# Cross-LogIO.net
KiCad netlist of a schematic drawn in Altium Designer
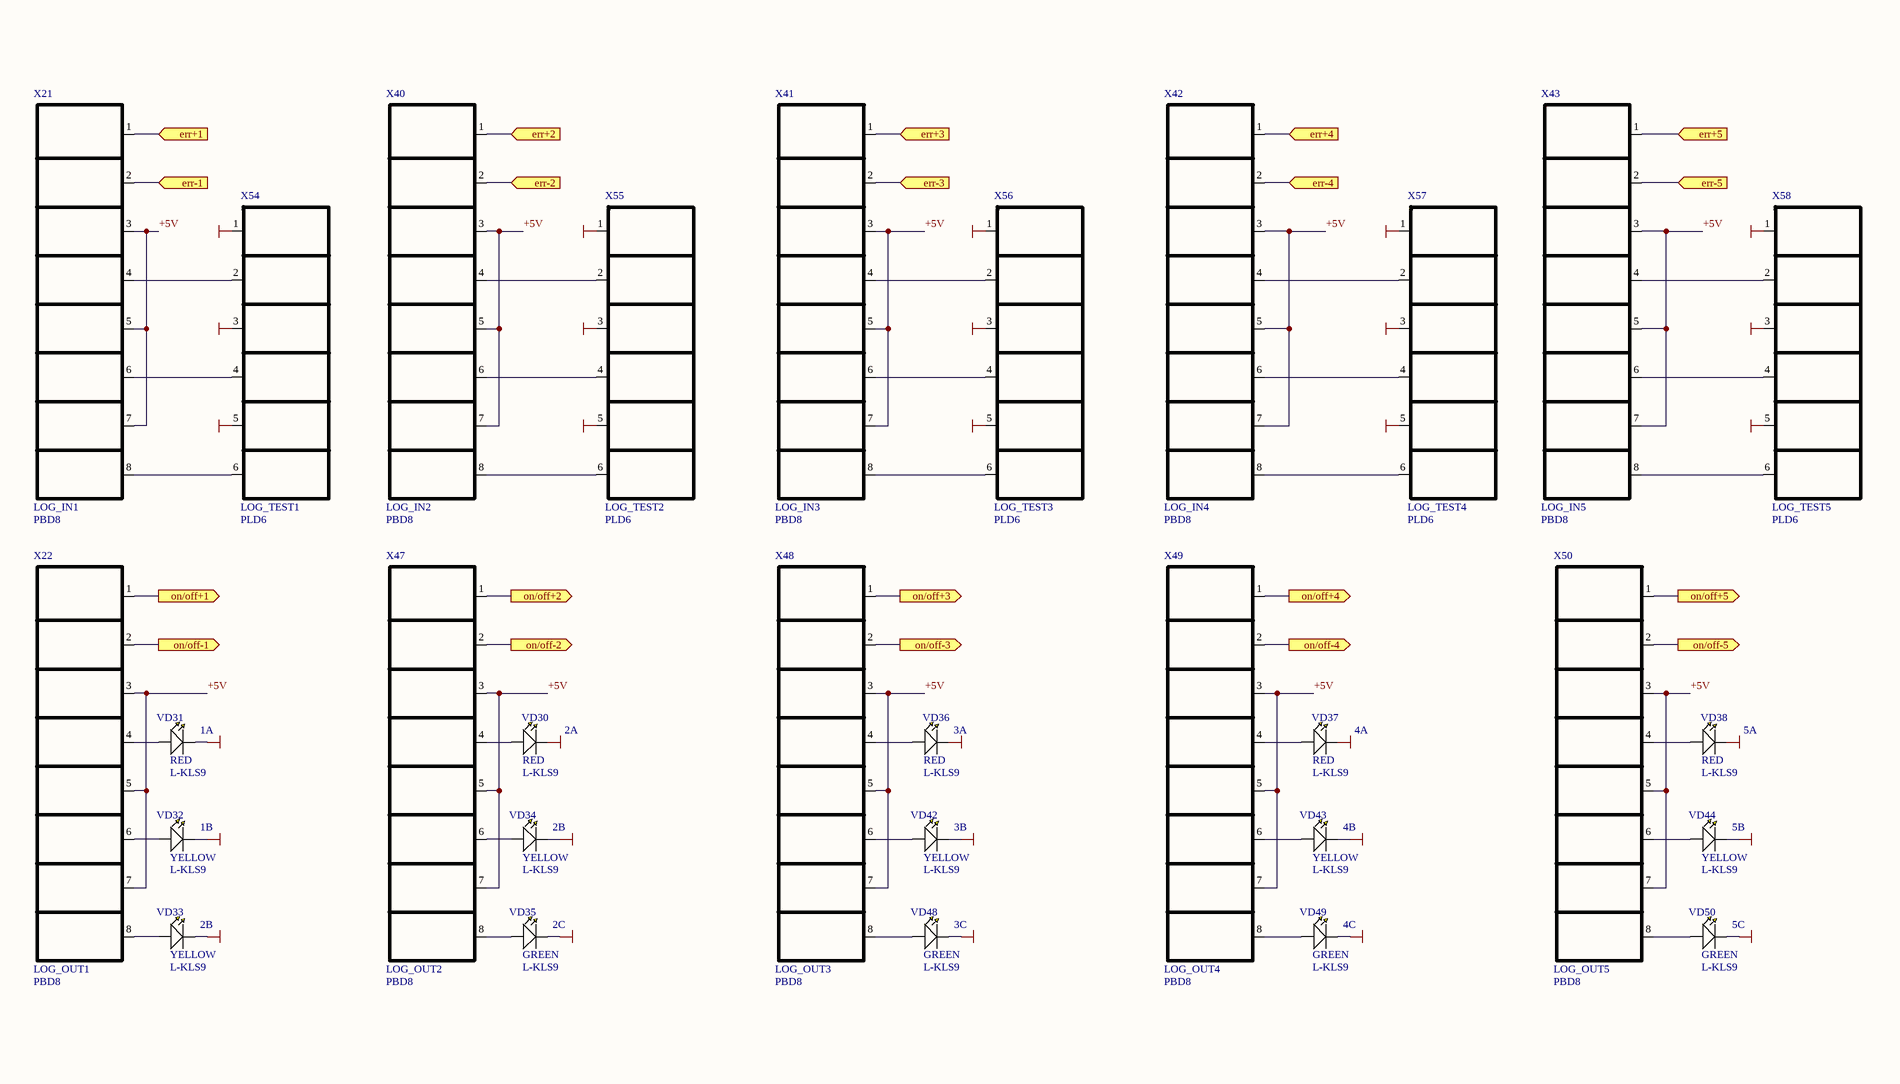
[diagram p0: Cross-LogIO.SchDoc, left]
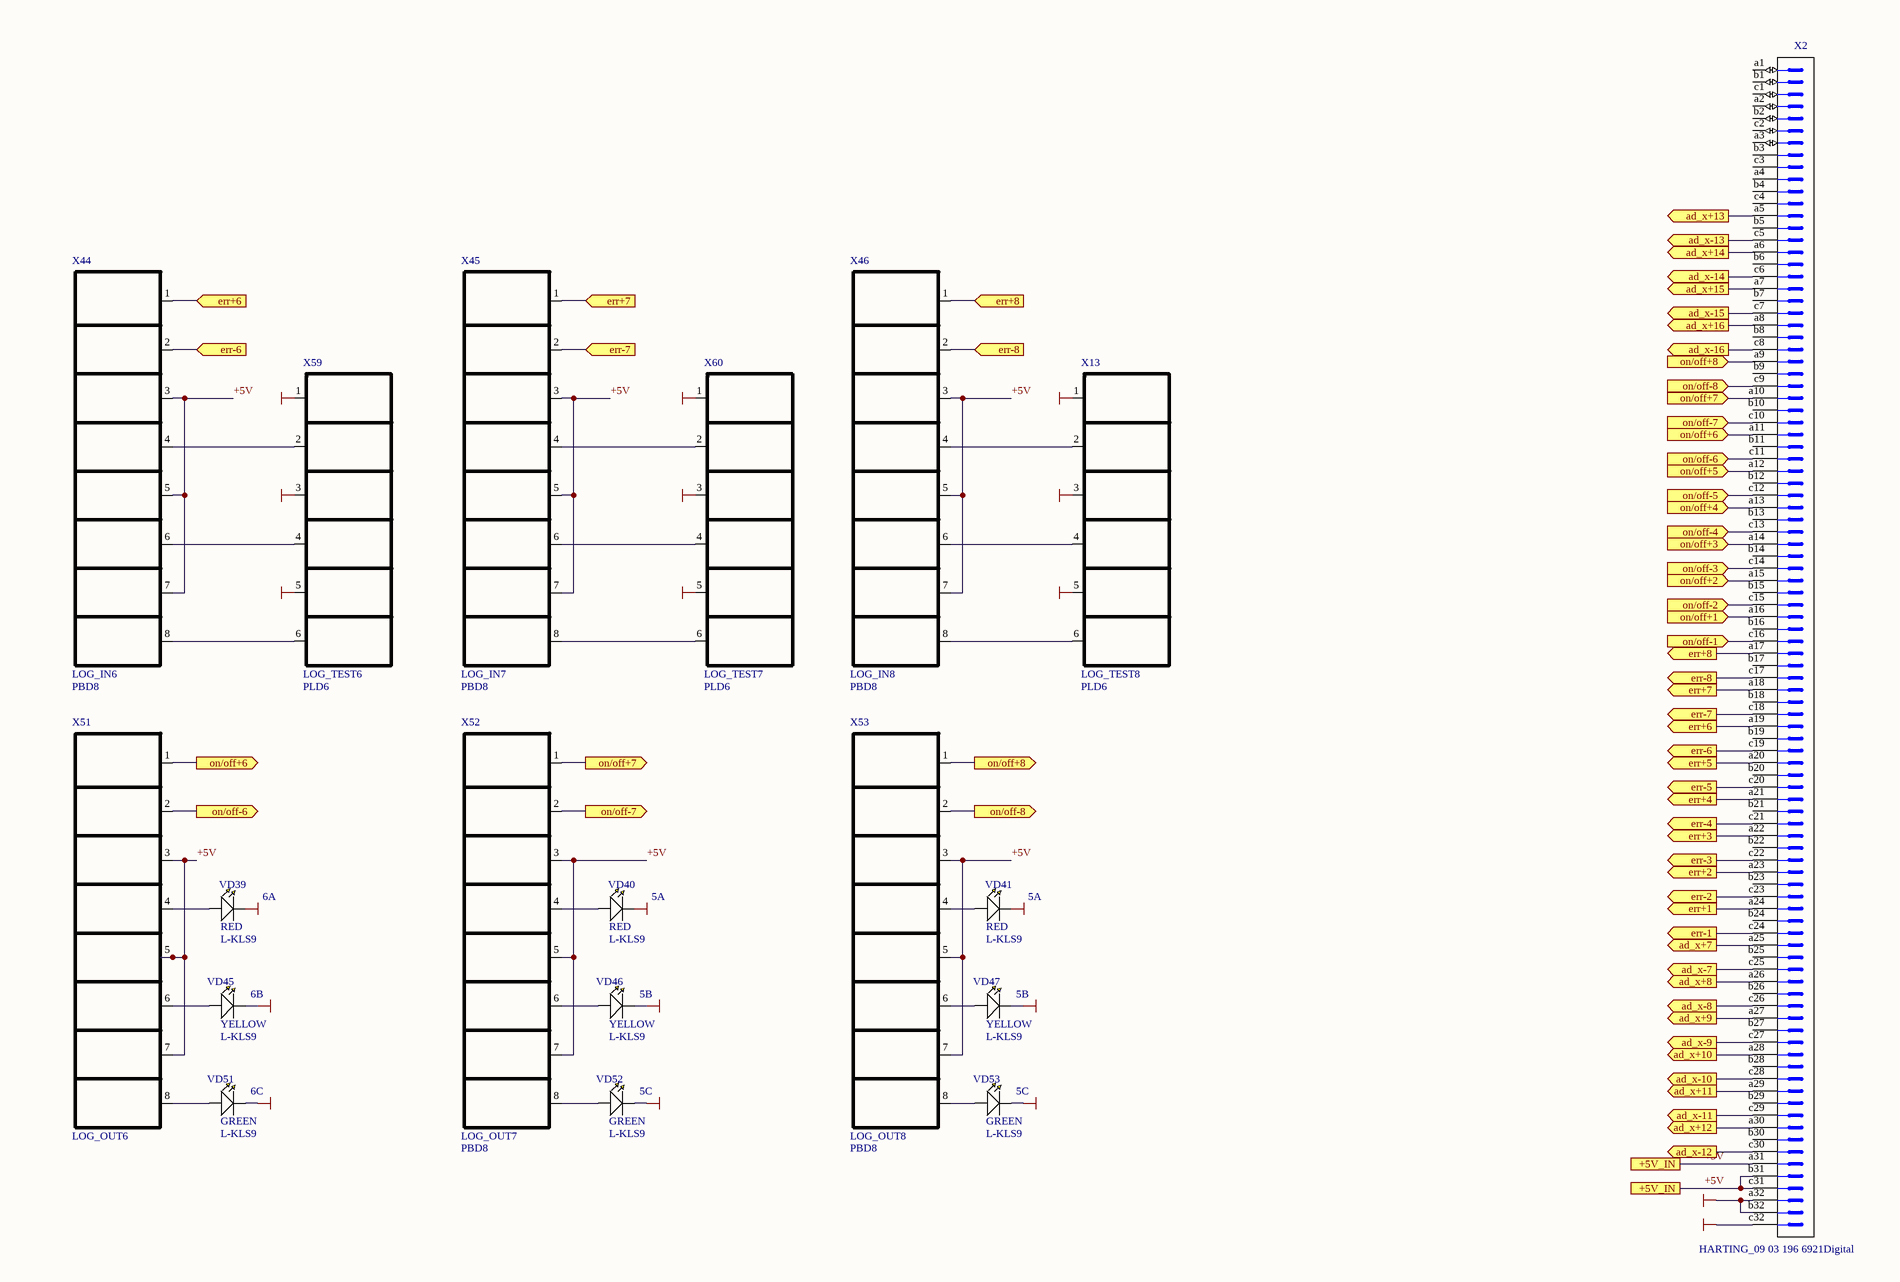
[diagram p1: Cross-LogIO.SchDoc, right]

(export (version "E")
  (design (tool "Eeschema 10.0.6"))
  (components
    (comp (ref "VD30")
      (value "2A")
      (footprint "LED0603")
      (description "Chip LED SMD 0603")
      (fields (field (name "COLOR") "RED") (field (name "DEVICE") "L-KLS9"))
      (libsource (lib "L1") (part "L-KLS9-T0603"))
    )
    (comp (ref "VD31")
      (value "1A")
      (footprint "LED0603")
      (description "Chip LED SMD 0603")
      (fields (field (name "COLOR") "RED") (field (name "DEVICE") "L-KLS9"))
      (libsource (lib "L1") (part "L-KLS9-T0603"))
    )
    (comp (ref "VD32")
      (value "1B")
      (footprint "LED0603")
      (description "Chip LED SMD 0603")
      (fields (field (name "COLOR") "YELLOW") (field (name "DEVICE") "L-KLS9"))
      (libsource (lib "L1") (part "L-KLS9-T0603"))
    )
    (comp (ref "VD33")
      (value "2B")
      (footprint "LED0603")
      (description "Chip LED SMD 0603")
      (fields (field (name "COLOR") "YELLOW") (field (name "DEVICE") "L-KLS9"))
      (libsource (lib "L1") (part "L-KLS9-T0603"))
    )
    (comp (ref "VD34")
      (value "2B")
      (footprint "LED0603")
      (description "Chip LED SMD 0603")
      (fields (field (name "COLOR") "YELLOW") (field (name "DEVICE") "L-KLS9"))
      (libsource (lib "L1") (part "L-KLS9-T0603"))
    )
    (comp (ref "VD35")
      (value "2C")
      (footprint "LED0603")
      (description "Chip LED SMD 0603")
      (fields (field (name "COLOR") "GREEN") (field (name "DEVICE") "L-KLS9"))
      (libsource (lib "L1") (part "L-KLS9-T0603"))
    )
    (comp (ref "VD36")
      (value "3A")
      (footprint "LED0603")
      (description "Chip LED SMD 0603")
      (fields (field (name "COLOR") "RED") (field (name "DEVICE") "L-KLS9"))
      (libsource (lib "L1") (part "L-KLS9-T0603"))
    )
    (comp (ref "VD37")
      (value "4A")
      (footprint "LED0603")
      (description "Chip LED SMD 0603")
      (fields (field (name "COLOR") "RED") (field (name "DEVICE") "L-KLS9"))
      (libsource (lib "L1") (part "L-KLS9-T0603"))
    )
    (comp (ref "VD38")
      (value "5A")
      (footprint "LED0603")
      (description "Chip LED SMD 0603")
      (fields (field (name "COLOR") "RED") (field (name "DEVICE") "L-KLS9"))
      (libsource (lib "L1") (part "L-KLS9-T0603"))
    )
    (comp (ref "VD39")
      (value "6A")
      (footprint "LED0603")
      (description "Chip LED SMD 0603")
      (fields (field (name "COLOR") "RED") (field (name "DEVICE") "L-KLS9"))
      (libsource (lib "L1") (part "L-KLS9-T0603"))
    )
    (comp (ref "VD40")
      (value "5A")
      (footprint "LED0603")
      (description "Chip LED SMD 0603")
      (fields (field (name "COLOR") "RED") (field (name "DEVICE") "L-KLS9"))
      (libsource (lib "L1") (part "L-KLS9-T0603"))
    )
    (comp (ref "VD41")
      (value "5A")
      (footprint "LED0603")
      (description "Chip LED SMD 0603")
      (fields (field (name "COLOR") "RED") (field (name "DEVICE") "L-KLS9"))
      (libsource (lib "L1") (part "L-KLS9-T0603"))
    )
    (comp (ref "VD42")
      (value "3B")
      (footprint "LED0603")
      (description "Chip LED SMD 0603")
      (fields (field (name "COLOR") "YELLOW") (field (name "DEVICE") "L-KLS9"))
      (libsource (lib "L1") (part "L-KLS9-T0603"))
    )
    (comp (ref "VD43")
      (value "4B")
      (footprint "LED0603")
      (description "Chip LED SMD 0603")
      (fields (field (name "COLOR") "YELLOW") (field (name "DEVICE") "L-KLS9"))
      (libsource (lib "L1") (part "L-KLS9-T0603"))
    )
    (comp (ref "VD44")
      (value "5B")
      (footprint "LED0603")
      (description "Chip LED SMD 0603")
      (fields (field (name "COLOR") "YELLOW") (field (name "DEVICE") "L-KLS9"))
      (libsource (lib "L1") (part "L-KLS9-T0603"))
    )
    (comp (ref "VD45")
      (value "6B")
      (footprint "LED0603")
      (description "Chip LED SMD 0603")
      (fields (field (name "COLOR") "YELLOW") (field (name "DEVICE") "L-KLS9"))
      (libsource (lib "L1") (part "L-KLS9-T0603"))
    )
    (comp (ref "VD46")
      (value "5B")
      (footprint "LED0603")
      (description "Chip LED SMD 0603")
      (fields (field (name "COLOR") "YELLOW") (field (name "DEVICE") "L-KLS9"))
      (libsource (lib "L1") (part "L-KLS9-T0603"))
    )
    (comp (ref "VD47")
      (value "5B")
      (footprint "LED0603")
      (description "Chip LED SMD 0603")
      (fields (field (name "COLOR") "YELLOW") (field (name "DEVICE") "L-KLS9"))
      (libsource (lib "L1") (part "L-KLS9-T0603"))
    )
    (comp (ref "VD48")
      (value "3C")
      (footprint "LED0603")
      (description "Chip LED SMD 0603")
      (fields (field (name "COLOR") "GREEN") (field (name "DEVICE") "L-KLS9"))
      (libsource (lib "L1") (part "L-KLS9-T0603"))
    )
    (comp (ref "VD49")
      (value "4C")
      (footprint "LED0603")
      (description "Chip LED SMD 0603")
      (fields (field (name "COLOR") "GREEN") (field (name "DEVICE") "L-KLS9"))
      (libsource (lib "L1") (part "L-KLS9-T0603"))
    )
    (comp (ref "VD50")
      (value "5C")
      (footprint "LED0603")
      (description "Chip LED SMD 0603")
      (fields (field (name "COLOR") "GREEN") (field (name "DEVICE") "L-KLS9"))
      (libsource (lib "L1") (part "L-KLS9-T0603"))
    )
    (comp (ref "VD51")
      (value "6C")
      (footprint "LED0603")
      (description "Chip LED SMD 0603")
      (fields (field (name "COLOR") "GREEN") (field (name "DEVICE") "L-KLS9"))
      (libsource (lib "L1") (part "L-KLS9-T0603"))
    )
    (comp (ref "VD52")
      (value "5C")
      (footprint "LED0603")
      (description "Chip LED SMD 0603")
      (fields (field (name "COLOR") "GREEN") (field (name "DEVICE") "L-KLS9"))
      (libsource (lib "L1") (part "L-KLS9-T0603"))
    )
    (comp (ref "VD53")
      (value "5C")
      (footprint "LED0603")
      (description "Chip LED SMD 0603")
      (fields (field (name "COLOR") "GREEN") (field (name "DEVICE") "L-KLS9"))
      (libsource (lib "L1") (part "L-KLS9-T0603"))
    )
    (comp (ref "X2")
      (value "HARTING_09 03 196 6921Digital")
      (footprint "HARTING_09 03 196 6921")
      (description "Connector 96 Male Right Angle")
      (libsource (lib "L1") (part "HARTING_09 03 196 6921"))
    )
    (comp (ref "X13")
      (value "LOG_TEST8")
      (footprint "DIP_6-254_WO_CASE")
      (description "6 pin TRH connector 2.54mm pitch")
      (fields (field (name "DEVICE") "PLD6"))
      (libsource (lib "L1") (part "PLD6"))
    )
    (comp (ref "X21")
      (value "LOG_IN1")
      (footprint "DIP_8-254_F")
      (description "8 pin TRH socket 2.54mm pitch")
      (fields (field (name "DEVICE") "PBD8"))
      (libsource (lib "L1") (part "PBD8"))
    )
    (comp (ref "X22")
      (value "LOG_OUT1")
      (footprint "DIP_8-254_F")
      (description "8 pin TRH socket 2.54mm pitch")
      (fields (field (name "DEVICE") "PBD8"))
      (libsource (lib "L1") (part "PBD8"))
    )
    (comp (ref "X40")
      (value "LOG_IN2")
      (footprint "DIP_8-254_F")
      (description "8 pin TRH socket 2.54mm pitch")
      (fields (field (name "DEVICE") "PBD8"))
      (libsource (lib "L1") (part "PBD8"))
    )
    (comp (ref "X41")
      (value "LOG_IN3")
      (footprint "DIP_8-254_F")
      (description "8 pin TRH socket 2.54mm pitch")
      (fields (field (name "DEVICE") "PBD8"))
      (libsource (lib "L1") (part "PBD8"))
    )
    (comp (ref "X42")
      (value "LOG_IN4")
      (footprint "DIP_8-254_F")
      (description "8 pin TRH socket 2.54mm pitch")
      (fields (field (name "DEVICE") "PBD8"))
      (libsource (lib "L1") (part "PBD8"))
    )
    (comp (ref "X43")
      (value "LOG_IN5")
      (footprint "DIP_8-254_F")
      (description "8 pin TRH socket 2.54mm pitch")
      (fields (field (name "DEVICE") "PBD8"))
      (libsource (lib "L1") (part "PBD8"))
    )
    (comp (ref "X44")
      (value "LOG_IN6")
      (footprint "DIP_8-254_F")
      (description "8 pin TRH socket 2.54mm pitch")
      (fields (field (name "DEVICE") "PBD8"))
      (libsource (lib "L1") (part "PBD8"))
    )
    (comp (ref "X45")
      (value "LOG_IN7")
      (footprint "DIP_8-254_F")
      (description "8 pin TRH socket 2.54mm pitch")
      (fields (field (name "DEVICE") "PBD8"))
      (libsource (lib "L1") (part "PBD8"))
    )
    (comp (ref "X46")
      (value "LOG_IN8")
      (footprint "DIP_8-254_F")
      (description "8 pin TRH socket 2.54mm pitch")
      (fields (field (name "DEVICE") "PBD8"))
      (libsource (lib "L1") (part "PBD8"))
    )
    (comp (ref "X47")
      (value "LOG_OUT2")
      (footprint "DIP_8-254_F")
      (description "8 pin TRH socket 2.54mm pitch")
      (fields (field (name "DEVICE") "PBD8"))
      (libsource (lib "L1") (part "PBD8"))
    )
    (comp (ref "X48")
      (value "LOG_OUT3")
      (footprint "DIP_8-254_F")
      (description "8 pin TRH socket 2.54mm pitch")
      (fields (field (name "DEVICE") "PBD8"))
      (libsource (lib "L1") (part "PBD8"))
    )
    (comp (ref "X49")
      (value "LOG_OUT4")
      (footprint "DIP_8-254_F")
      (description "8 pin TRH socket 2.54mm pitch")
      (fields (field (name "DEVICE") "PBD8"))
      (libsource (lib "L1") (part "PBD8"))
    )
    (comp (ref "X50")
      (value "LOG_OUT5")
      (footprint "DIP_8-254_F")
      (description "8 pin TRH socket 2.54mm pitch")
      (fields (field (name "DEVICE") "PBD8"))
      (libsource (lib "L1") (part "PBD8"))
    )
    (comp (ref "X51")
      (value "LOG_OUT6")
      (footprint "DIP_8-254_F")
      (description "8 pin TRH socket 2.54mm pitch")
      (libsource (lib "L1") (part "PBD8"))
    )
    (comp (ref "X52")
      (value "LOG_OUT7")
      (footprint "DIP_8-254_F")
      (description "8 pin TRH socket 2.54mm pitch")
      (fields (field (name "DEVICE") "PBD8"))
      (libsource (lib "L1") (part "PBD8"))
    )
    (comp (ref "X53")
      (value "LOG_OUT8")
      (footprint "DIP_8-254_F")
      (description "8 pin TRH socket 2.54mm pitch")
      (fields (field (name "DEVICE") "PBD8"))
      (libsource (lib "L1") (part "PBD8"))
    )
    (comp (ref "X54")
      (value "LOG_TEST1")
      (footprint "DIP_6-254_WO_CASE")
      (description "6 pin TRH connector 2.54mm pitch")
      (fields (field (name "DEVICE") "PLD6"))
      (libsource (lib "L1") (part "PLD6"))
    )
    (comp (ref "X55")
      (value "LOG_TEST2")
      (footprint "DIP_6-254_WO_CASE")
      (description "6 pin TRH connector 2.54mm pitch")
      (fields (field (name "DEVICE") "PLD6"))
      (libsource (lib "L1") (part "PLD6"))
    )
    (comp (ref "X56")
      (value "LOG_TEST3")
      (footprint "DIP_6-254_WO_CASE")
      (description "6 pin TRH connector 2.54mm pitch")
      (fields (field (name "DEVICE") "PLD6"))
      (libsource (lib "L1") (part "PLD6"))
    )
    (comp (ref "X57")
      (value "LOG_TEST4")
      (footprint "DIP_6-254_WO_CASE")
      (description "6 pin TRH connector 2.54mm pitch")
      (fields (field (name "DEVICE") "PLD6"))
      (libsource (lib "L1") (part "PLD6"))
    )
    (comp (ref "X58")
      (value "LOG_TEST5")
      (footprint "DIP_6-254_WO_CASE")
      (description "6 pin TRH connector 2.54mm pitch")
      (fields (field (name "DEVICE") "PLD6"))
      (libsource (lib "L1") (part "PLD6"))
    )
    (comp (ref "X59")
      (value "LOG_TEST6")
      (footprint "DIP_6-254_WO_CASE")
      (description "6 pin TRH connector 2.54mm pitch")
      (fields (field (name "DEVICE") "PLD6"))
      (libsource (lib "L1") (part "PLD6"))
    )
    (comp (ref "X60")
      (value "LOG_TEST7")
      (footprint "DIP_6-254_WO_CASE")
      (description "6 pin TRH connector 2.54mm pitch")
      (fields (field (name "DEVICE") "PLD6"))
      (libsource (lib "L1") (part "PLD6"))
    )
  )
  (nets
    (net (code "1") (name "/+5V") (class "Default")
      (node (ref "X2") (pin "a31") (pinfunction "a31_a31") (pintype "power_in"))
      (node (ref "X2") (pin "b31") (pinfunction "b31_b31") (pintype "power_in"))
      (node (ref "X2") (pin "c31") (pinfunction "c31_c31") (pintype "power_in"))
      (node (ref "X21") (pin "3") (pinfunction "3_3") (pintype "passive"))
      (node (ref "X21") (pin "5") (pinfunction "5_5") (pintype "passive"))
      (node (ref "X21") (pin "7") (pinfunction "7_7") (pintype "passive"))
      (node (ref "X22") (pin "3") (pinfunction "3_3") (pintype "passive"))
      (node (ref "X22") (pin "5") (pinfunction "5_5") (pintype "passive"))
      (node (ref "X22") (pin "7") (pinfunction "7_7") (pintype "passive"))
      (node (ref "X40") (pin "3") (pinfunction "3_3") (pintype "passive"))
      (node (ref "X40") (pin "5") (pinfunction "5_5") (pintype "passive"))
      (node (ref "X40") (pin "7") (pinfunction "7_7") (pintype "passive"))
      (node (ref "X41") (pin "3") (pinfunction "3_3") (pintype "passive"))
      (node (ref "X41") (pin "5") (pinfunction "5_5") (pintype "passive"))
      (node (ref "X41") (pin "7") (pinfunction "7_7") (pintype "passive"))
      (node (ref "X42") (pin "3") (pinfunction "3_3") (pintype "passive"))
      (node (ref "X42") (pin "5") (pinfunction "5_5") (pintype "passive"))
      (node (ref "X42") (pin "7") (pinfunction "7_7") (pintype "passive"))
      (node (ref "X43") (pin "3") (pinfunction "3_3") (pintype "passive"))
      (node (ref "X43") (pin "5") (pinfunction "5_5") (pintype "passive"))
      (node (ref "X43") (pin "7") (pinfunction "7_7") (pintype "passive"))
      (node (ref "X44") (pin "3") (pinfunction "3_3") (pintype "passive"))
      (node (ref "X44") (pin "5") (pinfunction "5_5") (pintype "passive"))
      (node (ref "X44") (pin "7") (pinfunction "7_7") (pintype "passive"))
      (node (ref "X45") (pin "3") (pinfunction "3_3") (pintype "passive"))
      (node (ref "X45") (pin "5") (pinfunction "5_5") (pintype "passive"))
      (node (ref "X45") (pin "7") (pinfunction "7_7") (pintype "passive"))
      (node (ref "X46") (pin "3") (pinfunction "3_3") (pintype "passive"))
      (node (ref "X46") (pin "5") (pinfunction "5_5") (pintype "passive"))
      (node (ref "X46") (pin "7") (pinfunction "7_7") (pintype "passive"))
      (node (ref "X47") (pin "3") (pinfunction "3_3") (pintype "passive"))
      (node (ref "X47") (pin "5") (pinfunction "5_5") (pintype "passive"))
      (node (ref "X47") (pin "7") (pinfunction "7_7") (pintype "passive"))
      (node (ref "X48") (pin "3") (pinfunction "3_3") (pintype "passive"))
      (node (ref "X48") (pin "5") (pinfunction "5_5") (pintype "passive"))
      (node (ref "X48") (pin "7") (pinfunction "7_7") (pintype "passive"))
      (node (ref "X49") (pin "3") (pinfunction "3_3") (pintype "passive"))
      (node (ref "X49") (pin "5") (pinfunction "5_5") (pintype "passive"))
      (node (ref "X49") (pin "7") (pinfunction "7_7") (pintype "passive"))
      (node (ref "X50") (pin "3") (pinfunction "3_3") (pintype "passive"))
      (node (ref "X50") (pin "5") (pinfunction "5_5") (pintype "passive"))
      (node (ref "X50") (pin "7") (pinfunction "7_7") (pintype "passive"))
      (node (ref "X51") (pin "3") (pinfunction "3_3") (pintype "passive"))
      (node (ref "X51") (pin "5") (pinfunction "5_5") (pintype "passive"))
      (node (ref "X51") (pin "7") (pinfunction "7_7") (pintype "passive"))
      (node (ref "X52") (pin "3") (pinfunction "3_3") (pintype "passive"))
      (node (ref "X52") (pin "5") (pinfunction "5_5") (pintype "passive"))
      (node (ref "X52") (pin "7") (pinfunction "7_7") (pintype "passive"))
      (node (ref "X53") (pin "3") (pinfunction "3_3") (pintype "passive"))
      (node (ref "X53") (pin "5") (pinfunction "5_5") (pintype "passive"))
      (node (ref "X53") (pin "7") (pinfunction "7_7") (pintype "passive"))
    )
    (net (code "2") (name "/ad_x+7") (class "Default")
      (node (ref "X2") (pin "a25") (pinfunction "a25_a25") (pintype "power_in"))
    )
    (net (code "3") (name "/ad_x+8") (class "Default")
      (node (ref "X2") (pin "a26") (pinfunction "a26_a26") (pintype "power_in"))
    )
    (net (code "4") (name "/ad_x+9") (class "Default")
      (node (ref "X2") (pin "a27") (pinfunction "a27_a27") (pintype "power_in"))
    )
    (net (code "5") (name "/ad_x+10") (class "Default")
      (node (ref "X2") (pin "a28") (pinfunction "a28_a28") (pintype "power_in"))
    )
    (net (code "6") (name "/ad_x+11") (class "Default")
      (node (ref "X2") (pin "a29") (pinfunction "a29_a29") (pintype "power_in"))
    )
    (net (code "7") (name "/ad_x+12") (class "Default")
      (node (ref "X2") (pin "a30") (pinfunction "a30_a30") (pintype "power_in"))
    )
    (net (code "8") (name "/ad_x+13") (class "Default")
      (node (ref "X2") (pin "a5") (pinfunction "a5_a5") (pintype "power_in"))
    )
    (net (code "9") (name "/ad_x+14") (class "Default")
      (node (ref "X2") (pin "a6") (pinfunction "a6_a6") (pintype "power_in"))
    )
    (net (code "10") (name "/ad_x+15") (class "Default")
      (node (ref "X2") (pin "a7") (pinfunction "a7_a7") (pintype "power_in"))
    )
    (net (code "11") (name "/ad_x+16") (class "Default")
      (node (ref "X2") (pin "a8") (pinfunction "a8_a8") (pintype "power_in"))
    )
    (net (code "12") (name "/ad_x-7") (class "Default")
      (node (ref "X2") (pin "c25") (pinfunction "c25_c25") (pintype "power_in"))
    )
    (net (code "13") (name "/ad_x-8") (class "Default")
      (node (ref "X2") (pin "c26") (pinfunction "c26_c26") (pintype "power_in"))
    )
    (net (code "14") (name "/ad_x-9") (class "Default")
      (node (ref "X2") (pin "c27") (pinfunction "c27_c27") (pintype "power_in"))
    )
    (net (code "15") (name "/ad_x-10") (class "Default")
      (node (ref "X2") (pin "c28") (pinfunction "c28_c28") (pintype "power_in"))
    )
    (net (code "16") (name "/ad_x-11") (class "Default")
      (node (ref "X2") (pin "c29") (pinfunction "c29_c29") (pintype "power_in"))
    )
    (net (code "17") (name "/ad_x-12") (class "Default")
      (node (ref "X2") (pin "c30") (pinfunction "c30_c30") (pintype "power_in"))
    )
    (net (code "18") (name "/ad_x-13") (class "Default")
      (node (ref "X2") (pin "c5") (pinfunction "c5_c5") (pintype "power_in"))
    )
    (net (code "19") (name "/ad_x-14") (class "Default")
      (node (ref "X2") (pin "c6") (pinfunction "c6_c6") (pintype "power_in"))
    )
    (net (code "20") (name "/ad_x-15") (class "Default")
      (node (ref "X2") (pin "c7") (pinfunction "c7_c7") (pintype "power_in"))
    )
    (net (code "21") (name "/ad_x-16") (class "Default")
      (node (ref "X2") (pin "c8") (pinfunction "c8_c8") (pintype "power_in"))
    )
    (net (code "22") (name "/err+1") (class "Default")
      (node (ref "X2") (pin "a24") (pinfunction "a24_a24") (pintype "power_in"))
      (node (ref "X21") (pin "1") (pinfunction "1_1") (pintype "passive"))
    )
    (net (code "23") (name "/err+2") (class "Default")
      (node (ref "X2") (pin "a23") (pinfunction "a23_a23") (pintype "power_in"))
      (node (ref "X40") (pin "1") (pinfunction "1_1") (pintype "passive"))
    )
    (net (code "24") (name "/err+3") (class "Default")
      (node (ref "X2") (pin "a22") (pinfunction "a22_a22") (pintype "power_in"))
      (node (ref "X41") (pin "1") (pinfunction "1_1") (pintype "passive"))
    )
    (net (code "25") (name "/err+4") (class "Default")
      (node (ref "X2") (pin "a21") (pinfunction "a21_a21") (pintype "power_in"))
      (node (ref "X42") (pin "1") (pinfunction "1_1") (pintype "passive"))
    )
    (net (code "26") (name "/err+5") (class "Default")
      (node (ref "X2") (pin "a20") (pinfunction "a20_a20") (pintype "power_in"))
      (node (ref "X43") (pin "1") (pinfunction "1_1") (pintype "passive"))
    )
    (net (code "27") (name "/err+6") (class "Default")
      (node (ref "X2") (pin "a19") (pinfunction "a19_a19") (pintype "power_in"))
      (node (ref "X44") (pin "1") (pinfunction "1_1") (pintype "passive"))
    )
    (net (code "28") (name "/err+7") (class "Default")
      (node (ref "X2") (pin "a18") (pinfunction "a18_a18") (pintype "power_in"))
      (node (ref "X45") (pin "1") (pinfunction "1_1") (pintype "passive"))
    )
    (net (code "29") (name "/err+8") (class "Default")
      (node (ref "X2") (pin "a17") (pinfunction "a17_a17") (pintype "power_in"))
      (node (ref "X46") (pin "1") (pinfunction "1_1") (pintype "passive"))
    )
    (net (code "30") (name "/err-1") (class "Default")
      (node (ref "X2") (pin "c24") (pinfunction "c24_c24") (pintype "power_in"))
      (node (ref "X21") (pin "2") (pinfunction "2_2") (pintype "passive"))
    )
    (net (code "31") (name "/err-2") (class "Default")
      (node (ref "X2") (pin "c23") (pinfunction "c23_c23") (pintype "power_in"))
      (node (ref "X40") (pin "2") (pinfunction "2_2") (pintype "passive"))
    )
    (net (code "32") (name "/err-3") (class "Default")
      (node (ref "X2") (pin "c22") (pinfunction "c22_c22") (pintype "power_in"))
      (node (ref "X41") (pin "2") (pinfunction "2_2") (pintype "passive"))
    )
    (net (code "33") (name "/err-4") (class "Default")
      (node (ref "X2") (pin "c21") (pinfunction "c21_c21") (pintype "power_in"))
      (node (ref "X42") (pin "2") (pinfunction "2_2") (pintype "passive"))
    )
    (net (code "34") (name "/err-5") (class "Default")
      (node (ref "X2") (pin "c20") (pinfunction "c20_c20") (pintype "power_in"))
      (node (ref "X43") (pin "2") (pinfunction "2_2") (pintype "passive"))
    )
    (net (code "35") (name "/err-6") (class "Default")
      (node (ref "X2") (pin "c19") (pinfunction "c19_c19") (pintype "power_in"))
      (node (ref "X44") (pin "2") (pinfunction "2_2") (pintype "passive"))
    )
    (net (code "36") (name "/err-7") (class "Default")
      (node (ref "X2") (pin "c18") (pinfunction "c18_c18") (pintype "power_in"))
      (node (ref "X45") (pin "2") (pinfunction "2_2") (pintype "passive"))
    )
    (net (code "37") (name "/err-8") (class "Default")
      (node (ref "X2") (pin "c17") (pinfunction "c17_c17") (pintype "power_in"))
      (node (ref "X46") (pin "2") (pinfunction "2_2") (pintype "passive"))
    )
    (net (code "38") (name "/on{slash}off+1") (class "Default")
      (node (ref "X2") (pin "a16") (pinfunction "a16_a16") (pintype "power_in"))
      (node (ref "X22") (pin "1") (pinfunction "1_1") (pintype "passive"))
    )
    (net (code "39") (name "/on{slash}off+2") (class "Default")
      (node (ref "X2") (pin "a15") (pinfunction "a15_a15") (pintype "power_in"))
      (node (ref "X47") (pin "1") (pinfunction "1_1") (pintype "passive"))
    )
    (net (code "40") (name "/on{slash}off+3") (class "Default")
      (node (ref "X2") (pin "a14") (pinfunction "a14_a14") (pintype "power_in"))
      (node (ref "X48") (pin "1") (pinfunction "1_1") (pintype "passive"))
    )
    (net (code "41") (name "/on{slash}off+4") (class "Default")
      (node (ref "X2") (pin "a13") (pinfunction "a13_a13") (pintype "power_in"))
      (node (ref "X49") (pin "1") (pinfunction "1_1") (pintype "passive"))
    )
    (net (code "42") (name "/on{slash}off+5") (class "Default")
      (node (ref "X2") (pin "a12") (pinfunction "a12_a12") (pintype "power_in"))
      (node (ref "X50") (pin "1") (pinfunction "1_1") (pintype "passive"))
    )
    (net (code "43") (name "/on{slash}off+6") (class "Default")
      (node (ref "X2") (pin "a11") (pinfunction "a11_a11") (pintype "power_in"))
      (node (ref "X51") (pin "1") (pinfunction "1_1") (pintype "passive"))
    )
    (net (code "44") (name "/on{slash}off+7") (class "Default")
      (node (ref "X2") (pin "a10") (pinfunction "a10_a10") (pintype "power_in"))
      (node (ref "X52") (pin "1") (pinfunction "1_1") (pintype "passive"))
    )
    (net (code "45") (name "/on{slash}off+8") (class "Default")
      (node (ref "X2") (pin "a9") (pinfunction "a9_a9") (pintype "power_in"))
      (node (ref "X53") (pin "1") (pinfunction "1_1") (pintype "passive"))
    )
    (net (code "46") (name "/on{slash}off-1") (class "Default")
      (node (ref "X2") (pin "c16") (pinfunction "c16_c16") (pintype "power_in"))
      (node (ref "X22") (pin "2") (pinfunction "2_2") (pintype "passive"))
    )
    (net (code "47") (name "/on{slash}off-2") (class "Default")
      (node (ref "X2") (pin "c15") (pinfunction "c15_c15") (pintype "power_in"))
      (node (ref "X47") (pin "2") (pinfunction "2_2") (pintype "passive"))
    )
    (net (code "48") (name "/on{slash}off-3") (class "Default")
      (node (ref "X2") (pin "c14") (pinfunction "c14_c14") (pintype "power_in"))
      (node (ref "X48") (pin "2") (pinfunction "2_2") (pintype "passive"))
    )
    (net (code "49") (name "/on{slash}off-4") (class "Default")
      (node (ref "X2") (pin "c13") (pinfunction "c13_c13") (pintype "power_in"))
      (node (ref "X49") (pin "2") (pinfunction "2_2") (pintype "passive"))
    )
    (net (code "50") (name "/on{slash}off-5") (class "Default")
      (node (ref "X2") (pin "c12") (pinfunction "c12_c12") (pintype "power_in"))
      (node (ref "X50") (pin "2") (pinfunction "2_2") (pintype "passive"))
    )
    (net (code "51") (name "/on{slash}off-6") (class "Default")
      (node (ref "X2") (pin "c11") (pinfunction "c11_c11") (pintype "power_in"))
      (node (ref "X51") (pin "2") (pinfunction "2_2") (pintype "passive"))
    )
    (net (code "52") (name "/on{slash}off-7") (class "Default")
      (node (ref "X2") (pin "c10") (pinfunction "c10_c10") (pintype "power_in"))
      (node (ref "X52") (pin "2") (pinfunction "2_2") (pintype "passive"))
    )
    (net (code "53") (name "/on{slash}off-8") (class "Default")
      (node (ref "X2") (pin "c9") (pinfunction "c9_c9") (pintype "power_in"))
      (node (ref "X53") (pin "2") (pinfunction "2_2") (pintype "passive"))
    )
    (net (code "54") (name "GND") (class "Default")
      (node (ref "VD30") (pin "1") (pinfunction "C_1") (pintype "passive"))
      (node (ref "VD31") (pin "1") (pinfunction "C_1") (pintype "passive"))
      (node (ref "VD32") (pin "1") (pinfunction "C_1") (pintype "passive"))
      (node (ref "VD33") (pin "1") (pinfunction "C_1") (pintype "passive"))
      (node (ref "VD34") (pin "1") (pinfunction "C_1") (pintype "passive"))
      (node (ref "VD35") (pin "1") (pinfunction "C_1") (pintype "passive"))
      (node (ref "VD36") (pin "1") (pinfunction "C_1") (pintype "passive"))
      (node (ref "VD37") (pin "1") (pinfunction "C_1") (pintype "passive"))
      (node (ref "VD38") (pin "1") (pinfunction "C_1") (pintype "passive"))
      (node (ref "VD39") (pin "1") (pinfunction "C_1") (pintype "passive"))
      (node (ref "VD40") (pin "1") (pinfunction "C_1") (pintype "passive"))
      (node (ref "VD41") (pin "1") (pinfunction "C_1") (pintype "passive"))
      (node (ref "VD42") (pin "1") (pinfunction "C_1") (pintype "passive"))
      (node (ref "VD43") (pin "1") (pinfunction "C_1") (pintype "passive"))
      (node (ref "VD44") (pin "1") (pinfunction "C_1") (pintype "passive"))
      (node (ref "VD45") (pin "1") (pinfunction "C_1") (pintype "passive"))
      (node (ref "VD46") (pin "1") (pinfunction "C_1") (pintype "passive"))
      (node (ref "VD47") (pin "1") (pinfunction "C_1") (pintype "passive"))
      (node (ref "VD48") (pin "1") (pinfunction "C_1") (pintype "passive"))
      (node (ref "VD49") (pin "1") (pinfunction "C_1") (pintype "passive"))
      (node (ref "VD50") (pin "1") (pinfunction "C_1") (pintype "passive"))
      (node (ref "VD51") (pin "1") (pinfunction "C_1") (pintype "passive"))
      (node (ref "VD52") (pin "1") (pinfunction "C_1") (pintype "passive"))
      (node (ref "VD53") (pin "1") (pinfunction "C_1") (pintype "passive"))
      (node (ref "X13") (pin "1") (pinfunction "1_1") (pintype "passive"))
      (node (ref "X13") (pin "3") (pinfunction "3_3") (pintype "passive"))
      (node (ref "X13") (pin "5") (pinfunction "5_5") (pintype "passive"))
      (node (ref "X2") (pin "a32") (pinfunction "a32_a32") (pintype "power_in"))
      (node (ref "X2") (pin "b32") (pinfunction "b32_b32") (pintype "power_in"))
      (node (ref "X2") (pin "c32") (pinfunction "c32_c32") (pintype "power_in"))
      (node (ref "X54") (pin "1") (pinfunction "1_1") (pintype "passive"))
      (node (ref "X54") (pin "3") (pinfunction "3_3") (pintype "passive"))
      (node (ref "X54") (pin "5") (pinfunction "5_5") (pintype "passive"))
      (node (ref "X55") (pin "1") (pinfunction "1_1") (pintype "passive"))
      (node (ref "X55") (pin "3") (pinfunction "3_3") (pintype "passive"))
      (node (ref "X55") (pin "5") (pinfunction "5_5") (pintype "passive"))
      (node (ref "X56") (pin "1") (pinfunction "1_1") (pintype "passive"))
      (node (ref "X56") (pin "3") (pinfunction "3_3") (pintype "passive"))
      (node (ref "X56") (pin "5") (pinfunction "5_5") (pintype "passive"))
      (node (ref "X57") (pin "1") (pinfunction "1_1") (pintype "passive"))
      (node (ref "X57") (pin "3") (pinfunction "3_3") (pintype "passive"))
      (node (ref "X57") (pin "5") (pinfunction "5_5") (pintype "passive"))
      (node (ref "X58") (pin "1") (pinfunction "1_1") (pintype "passive"))
      (node (ref "X58") (pin "3") (pinfunction "3_3") (pintype "passive"))
      (node (ref "X58") (pin "5") (pinfunction "5_5") (pintype "passive"))
      (node (ref "X59") (pin "1") (pinfunction "1_1") (pintype "passive"))
      (node (ref "X59") (pin "3") (pinfunction "3_3") (pintype "passive"))
      (node (ref "X59") (pin "5") (pinfunction "5_5") (pintype "passive"))
      (node (ref "X60") (pin "1") (pinfunction "1_1") (pintype "passive"))
      (node (ref "X60") (pin "3") (pinfunction "3_3") (pintype "passive"))
      (node (ref "X60") (pin "5") (pinfunction "5_5") (pintype "passive"))
    )
    (net (code "55") (name "Net-(VD30-A)") (class "Default")
      (node (ref "VD30") (pin "2") (pinfunction "A_2") (pintype "passive"))
      (node (ref "X47") (pin "4") (pinfunction "4_4") (pintype "passive"))
    )
    (net (code "56") (name "Net-(VD31-A)") (class "Default")
      (node (ref "VD31") (pin "2") (pinfunction "A_2") (pintype "passive"))
      (node (ref "X22") (pin "4") (pinfunction "4_4") (pintype "passive"))
    )
    (net (code "57") (name "Net-(VD32-A)") (class "Default")
      (node (ref "VD32") (pin "2") (pinfunction "A_2") (pintype "passive"))
      (node (ref "X22") (pin "6") (pinfunction "6_6") (pintype "passive"))
    )
    (net (code "58") (name "Net-(VD33-A)") (class "Default")
      (node (ref "VD33") (pin "2") (pinfunction "A_2") (pintype "passive"))
      (node (ref "X22") (pin "8") (pinfunction "8_8") (pintype "passive"))
    )
    (net (code "59") (name "Net-(VD34-A)") (class "Default")
      (node (ref "VD34") (pin "2") (pinfunction "A_2") (pintype "passive"))
      (node (ref "X47") (pin "6") (pinfunction "6_6") (pintype "passive"))
    )
    (net (code "60") (name "Net-(VD35-A)") (class "Default")
      (node (ref "VD35") (pin "2") (pinfunction "A_2") (pintype "passive"))
      (node (ref "X47") (pin "8") (pinfunction "8_8") (pintype "passive"))
    )
    (net (code "61") (name "Net-(VD36-A)") (class "Default")
      (node (ref "VD36") (pin "2") (pinfunction "A_2") (pintype "passive"))
      (node (ref "X48") (pin "4") (pinfunction "4_4") (pintype "passive"))
    )
    (net (code "62") (name "Net-(VD37-A)") (class "Default")
      (node (ref "VD37") (pin "2") (pinfunction "A_2") (pintype "passive"))
      (node (ref "X49") (pin "4") (pinfunction "4_4") (pintype "passive"))
    )
    (net (code "63") (name "Net-(VD38-A)") (class "Default")
      (node (ref "VD38") (pin "2") (pinfunction "A_2") (pintype "passive"))
      (node (ref "X50") (pin "4") (pinfunction "4_4") (pintype "passive"))
    )
    (net (code "64") (name "Net-(VD39-A)") (class "Default")
      (node (ref "VD39") (pin "2") (pinfunction "A_2") (pintype "passive"))
      (node (ref "X51") (pin "4") (pinfunction "4_4") (pintype "passive"))
    )
    (net (code "65") (name "Net-(VD40-A)") (class "Default")
      (node (ref "VD40") (pin "2") (pinfunction "A_2") (pintype "passive"))
      (node (ref "X52") (pin "4") (pinfunction "4_4") (pintype "passive"))
    )
    (net (code "66") (name "Net-(VD41-A)") (class "Default")
      (node (ref "VD41") (pin "2") (pinfunction "A_2") (pintype "passive"))
      (node (ref "X53") (pin "4") (pinfunction "4_4") (pintype "passive"))
    )
    (net (code "67") (name "Net-(VD42-A)") (class "Default")
      (node (ref "VD42") (pin "2") (pinfunction "A_2") (pintype "passive"))
      (node (ref "X48") (pin "6") (pinfunction "6_6") (pintype "passive"))
    )
    (net (code "68") (name "Net-(VD43-A)") (class "Default")
      (node (ref "VD43") (pin "2") (pinfunction "A_2") (pintype "passive"))
      (node (ref "X49") (pin "6") (pinfunction "6_6") (pintype "passive"))
    )
    (net (code "69") (name "Net-(VD44-A)") (class "Default")
      (node (ref "VD44") (pin "2") (pinfunction "A_2") (pintype "passive"))
      (node (ref "X50") (pin "6") (pinfunction "6_6") (pintype "passive"))
    )
    (net (code "70") (name "Net-(VD45-A)") (class "Default")
      (node (ref "VD45") (pin "2") (pinfunction "A_2") (pintype "passive"))
      (node (ref "X51") (pin "6") (pinfunction "6_6") (pintype "passive"))
    )
    (net (code "71") (name "Net-(VD46-A)") (class "Default")
      (node (ref "VD46") (pin "2") (pinfunction "A_2") (pintype "passive"))
      (node (ref "X52") (pin "6") (pinfunction "6_6") (pintype "passive"))
    )
    (net (code "72") (name "Net-(VD47-A)") (class "Default")
      (node (ref "VD47") (pin "2") (pinfunction "A_2") (pintype "passive"))
      (node (ref "X53") (pin "6") (pinfunction "6_6") (pintype "passive"))
    )
    (net (code "73") (name "Net-(VD48-A)") (class "Default")
      (node (ref "VD48") (pin "2") (pinfunction "A_2") (pintype "passive"))
      (node (ref "X48") (pin "8") (pinfunction "8_8") (pintype "passive"))
    )
    (net (code "74") (name "Net-(VD49-A)") (class "Default")
      (node (ref "VD49") (pin "2") (pinfunction "A_2") (pintype "passive"))
      (node (ref "X49") (pin "8") (pinfunction "8_8") (pintype "passive"))
    )
    (net (code "75") (name "Net-(VD50-A)") (class "Default")
      (node (ref "VD50") (pin "2") (pinfunction "A_2") (pintype "passive"))
      (node (ref "X50") (pin "8") (pinfunction "8_8") (pintype "passive"))
    )
    (net (code "76") (name "Net-(VD51-A)") (class "Default")
      (node (ref "VD51") (pin "2") (pinfunction "A_2") (pintype "passive"))
      (node (ref "X51") (pin "8") (pinfunction "8_8") (pintype "passive"))
    )
    (net (code "77") (name "Net-(VD52-A)") (class "Default")
      (node (ref "VD52") (pin "2") (pinfunction "A_2") (pintype "passive"))
      (node (ref "X52") (pin "8") (pinfunction "8_8") (pintype "passive"))
    )
    (net (code "78") (name "Net-(VD53-A)") (class "Default")
      (node (ref "VD53") (pin "2") (pinfunction "A_2") (pintype "passive"))
      (node (ref "X53") (pin "8") (pinfunction "8_8") (pintype "passive"))
    )
    (net (code "79") (name "Net-(X13-Pad2)") (class "Default")
      (node (ref "X13") (pin "2") (pinfunction "2_2") (pintype "passive"))
      (node (ref "X46") (pin "4") (pinfunction "4_4") (pintype "passive"))
    )
    (net (code "80") (name "Net-(X13-Pad4)") (class "Default")
      (node (ref "X13") (pin "4") (pinfunction "4_4") (pintype "passive"))
      (node (ref "X46") (pin "6") (pinfunction "6_6") (pintype "passive"))
    )
    (net (code "81") (name "Net-(X13-Pad6)") (class "Default")
      (node (ref "X13") (pin "6") (pinfunction "6_6") (pintype "passive"))
      (node (ref "X46") (pin "8") (pinfunction "8_8") (pintype "passive"))
    )
    (net (code "82") (name "Net-(X21-Pad4)") (class "Default")
      (node (ref "X21") (pin "4") (pinfunction "4_4") (pintype "passive"))
      (node (ref "X54") (pin "2") (pinfunction "2_2") (pintype "passive"))
    )
    (net (code "83") (name "Net-(X21-Pad6)") (class "Default")
      (node (ref "X21") (pin "6") (pinfunction "6_6") (pintype "passive"))
      (node (ref "X54") (pin "4") (pinfunction "4_4") (pintype "passive"))
    )
    (net (code "84") (name "Net-(X21-Pad8)") (class "Default")
      (node (ref "X21") (pin "8") (pinfunction "8_8") (pintype "passive"))
      (node (ref "X54") (pin "6") (pinfunction "6_6") (pintype "passive"))
    )
    (net (code "85") (name "Net-(X40-Pad4)") (class "Default")
      (node (ref "X40") (pin "4") (pinfunction "4_4") (pintype "passive"))
      (node (ref "X55") (pin "2") (pinfunction "2_2") (pintype "passive"))
    )
    (net (code "86") (name "Net-(X40-Pad6)") (class "Default")
      (node (ref "X40") (pin "6") (pinfunction "6_6") (pintype "passive"))
      (node (ref "X55") (pin "4") (pinfunction "4_4") (pintype "passive"))
    )
    (net (code "87") (name "Net-(X40-Pad8)") (class "Default")
      (node (ref "X40") (pin "8") (pinfunction "8_8") (pintype "passive"))
      (node (ref "X55") (pin "6") (pinfunction "6_6") (pintype "passive"))
    )
    (net (code "88") (name "Net-(X41-Pad4)") (class "Default")
      (node (ref "X41") (pin "4") (pinfunction "4_4") (pintype "passive"))
      (node (ref "X56") (pin "2") (pinfunction "2_2") (pintype "passive"))
    )
    (net (code "89") (name "Net-(X41-Pad6)") (class "Default")
      (node (ref "X41") (pin "6") (pinfunction "6_6") (pintype "passive"))
      (node (ref "X56") (pin "4") (pinfunction "4_4") (pintype "passive"))
    )
    (net (code "90") (name "Net-(X41-Pad8)") (class "Default")
      (node (ref "X41") (pin "8") (pinfunction "8_8") (pintype "passive"))
      (node (ref "X56") (pin "6") (pinfunction "6_6") (pintype "passive"))
    )
    (net (code "91") (name "Net-(X42-Pad4)") (class "Default")
      (node (ref "X42") (pin "4") (pinfunction "4_4") (pintype "passive"))
      (node (ref "X57") (pin "2") (pinfunction "2_2") (pintype "passive"))
    )
    (net (code "92") (name "Net-(X42-Pad6)") (class "Default")
      (node (ref "X42") (pin "6") (pinfunction "6_6") (pintype "passive"))
      (node (ref "X57") (pin "4") (pinfunction "4_4") (pintype "passive"))
    )
    (net (code "93") (name "Net-(X42-Pad8)") (class "Default")
      (node (ref "X42") (pin "8") (pinfunction "8_8") (pintype "passive"))
      (node (ref "X57") (pin "6") (pinfunction "6_6") (pintype "passive"))
    )
    (net (code "94") (name "Net-(X43-Pad4)") (class "Default")
      (node (ref "X43") (pin "4") (pinfunction "4_4") (pintype "passive"))
      (node (ref "X58") (pin "2") (pinfunction "2_2") (pintype "passive"))
    )
    (net (code "95") (name "Net-(X43-Pad6)") (class "Default")
      (node (ref "X43") (pin "6") (pinfunction "6_6") (pintype "passive"))
      (node (ref "X58") (pin "4") (pinfunction "4_4") (pintype "passive"))
    )
    (net (code "96") (name "Net-(X43-Pad8)") (class "Default")
      (node (ref "X43") (pin "8") (pinfunction "8_8") (pintype "passive"))
      (node (ref "X58") (pin "6") (pinfunction "6_6") (pintype "passive"))
    )
    (net (code "97") (name "Net-(X44-Pad4)") (class "Default")
      (node (ref "X44") (pin "4") (pinfunction "4_4") (pintype "passive"))
      (node (ref "X59") (pin "2") (pinfunction "2_2") (pintype "passive"))
    )
    (net (code "98") (name "Net-(X44-Pad6)") (class "Default")
      (node (ref "X44") (pin "6") (pinfunction "6_6") (pintype "passive"))
      (node (ref "X59") (pin "4") (pinfunction "4_4") (pintype "passive"))
    )
    (net (code "99") (name "Net-(X44-Pad8)") (class "Default")
      (node (ref "X44") (pin "8") (pinfunction "8_8") (pintype "passive"))
      (node (ref "X59") (pin "6") (pinfunction "6_6") (pintype "passive"))
    )
    (net (code "100") (name "Net-(X45-Pad4)") (class "Default")
      (node (ref "X45") (pin "4") (pinfunction "4_4") (pintype "passive"))
      (node (ref "X60") (pin "2") (pinfunction "2_2") (pintype "passive"))
    )
    (net (code "101") (name "Net-(X45-Pad6)") (class "Default")
      (node (ref "X45") (pin "6") (pinfunction "6_6") (pintype "passive"))
      (node (ref "X60") (pin "4") (pinfunction "4_4") (pintype "passive"))
    )
    (net (code "102") (name "Net-(X45-Pad8)") (class "Default")
      (node (ref "X45") (pin "8") (pinfunction "8_8") (pintype "passive"))
      (node (ref "X60") (pin "6") (pinfunction "6_6") (pintype "passive"))
    )
    (net (code "103") (name "unconnected-(X2-5-Padb2)") (class "Default")
      (node (ref "X2") (pin "b2") (pinfunction "5_b2") (pintype "bidirectional"))
    )
    (net (code "104") (name "unconnected-(X2-Pada1)") (class "Default")
      (node (ref "X2") (pin "a1") (pinfunction "a1_a1") (pintype "bidirectional"))
    )
    (net (code "105") (name "unconnected-(X2-Pada2)") (class "Default")
      (node (ref "X2") (pin "a2") (pinfunction "a2_a2") (pintype "bidirectional"))
    )
    (net (code "106") (name "unconnected-(X2-Pada3)") (class "Default")
      (node (ref "X2") (pin "a3") (pinfunction "a3_a3") (pintype "bidirectional"))
    )
    (net (code "107") (name "unconnected-(X2-Pada4)") (class "Default")
      (node (ref "X2") (pin "a4") (pinfunction "a4_a4") (pintype "power_in"))
    )
    (net (code "108") (name "unconnected-(X2-Padb1)") (class "Default")
      (node (ref "X2") (pin "b1") (pinfunction "b1_b1") (pintype "bidirectional"))
    )
    (net (code "109") (name "unconnected-(X2-Padb3)") (class "Default")
      (node (ref "X2") (pin "b3") (pinfunction "b3_b3") (pintype "power_in"))
    )
    (net (code "110") (name "unconnected-(X2-Padb4)") (class "Default")
      (node (ref "X2") (pin "b4") (pinfunction "b4_b4") (pintype "power_in"))
    )
    (net (code "111") (name "unconnected-(X2-Padb5)") (class "Default")
      (node (ref "X2") (pin "b5") (pinfunction "b5_b5") (pintype "power_in"))
    )
    (net (code "112") (name "unconnected-(X2-Padb6)") (class "Default")
      (node (ref "X2") (pin "b6") (pinfunction "b6_b6") (pintype "power_in"))
    )
    (net (code "113") (name "unconnected-(X2-Padb7)") (class "Default")
      (node (ref "X2") (pin "b7") (pinfunction "b7_b7") (pintype "power_in"))
    )
    (net (code "114") (name "unconnected-(X2-Padb8)") (class "Default")
      (node (ref "X2") (pin "b8") (pinfunction "b8_b8") (pintype "power_in"))
    )
    (net (code "115") (name "unconnected-(X2-Padb9)") (class "Default")
      (node (ref "X2") (pin "b9") (pinfunction "b9_b9") (pintype "power_in"))
    )
    (net (code "116") (name "unconnected-(X2-Padb10)") (class "Default")
      (node (ref "X2") (pin "b10") (pinfunction "b10_b10") (pintype "power_in"))
    )
    (net (code "117") (name "unconnected-(X2-Padb11)") (class "Default")
      (node (ref "X2") (pin "b11") (pinfunction "b11_b11") (pintype "power_in"))
    )
    (net (code "118") (name "unconnected-(X2-Padb12)") (class "Default")
      (node (ref "X2") (pin "b12") (pinfunction "b12_b12") (pintype "power_in"))
    )
    (net (code "119") (name "unconnected-(X2-Padb13)") (class "Default")
      (node (ref "X2") (pin "b13") (pinfunction "b13_b13") (pintype "power_in"))
    )
    (net (code "120") (name "unconnected-(X2-Padb14)") (class "Default")
      (node (ref "X2") (pin "b14") (pinfunction "b14_b14") (pintype "power_in"))
    )
    (net (code "121") (name "unconnected-(X2-Padb15)") (class "Default")
      (node (ref "X2") (pin "b15") (pinfunction "b15_b15") (pintype "power_in"))
    )
    (net (code "122") (name "unconnected-(X2-Padb16)") (class "Default")
      (node (ref "X2") (pin "b16") (pinfunction "b16_b16") (pintype "power_in"))
    )
    (net (code "123") (name "unconnected-(X2-Padb17)") (class "Default")
      (node (ref "X2") (pin "b17") (pinfunction "b17_b17") (pintype "power_in"))
    )
    (net (code "124") (name "unconnected-(X2-Padb18)") (class "Default")
      (node (ref "X2") (pin "b18") (pinfunction "b18_b18") (pintype "power_in"))
    )
    (net (code "125") (name "unconnected-(X2-Padb19)") (class "Default")
      (node (ref "X2") (pin "b19") (pinfunction "b19_b19") (pintype "power_in"))
    )
    (net (code "126") (name "unconnected-(X2-Padb20)") (class "Default")
      (node (ref "X2") (pin "b20") (pinfunction "b20_b20") (pintype "power_in"))
    )
    (net (code "127") (name "unconnected-(X2-Padb21)") (class "Default")
      (node (ref "X2") (pin "b21") (pinfunction "b21_b21") (pintype "power_in"))
    )
    (net (code "128") (name "unconnected-(X2-Padb22)") (class "Default")
      (node (ref "X2") (pin "b22") (pinfunction "b22_b22") (pintype "power_in"))
    )
    (net (code "129") (name "unconnected-(X2-Padb23)") (class "Default")
      (node (ref "X2") (pin "b23") (pinfunction "b23_b23") (pintype "power_in"))
    )
    (net (code "130") (name "unconnected-(X2-Padb24)") (class "Default")
      (node (ref "X2") (pin "b24") (pinfunction "b24_b24") (pintype "power_in"))
    )
    (net (code "131") (name "unconnected-(X2-Padb25)") (class "Default")
      (node (ref "X2") (pin "b25") (pinfunction "b25_b25") (pintype "power_in"))
    )
    (net (code "132") (name "unconnected-(X2-Padb26)") (class "Default")
      (node (ref "X2") (pin "b26") (pinfunction "b26_b26") (pintype "power_in"))
    )
    (net (code "133") (name "unconnected-(X2-Padb27)") (class "Default")
      (node (ref "X2") (pin "b27") (pinfunction "b27_b27") (pintype "power_in"))
    )
    (net (code "134") (name "unconnected-(X2-Padb28)") (class "Default")
      (node (ref "X2") (pin "b28") (pinfunction "b28_b28") (pintype "power_in"))
    )
    (net (code "135") (name "unconnected-(X2-Padb29)") (class "Default")
      (node (ref "X2") (pin "b29") (pinfunction "b29_b29") (pintype "power_in"))
    )
    (net (code "136") (name "unconnected-(X2-Padb30)") (class "Default")
      (node (ref "X2") (pin "b30") (pinfunction "b30_b30") (pintype "power_in"))
    )
    (net (code "137") (name "unconnected-(X2-Padc1)") (class "Default")
      (node (ref "X2") (pin "c1") (pinfunction "c1_c1") (pintype "bidirectional"))
    )
    (net (code "138") (name "unconnected-(X2-Padc2)") (class "Default")
      (node (ref "X2") (pin "c2") (pinfunction "c2_c2") (pintype "bidirectional"))
    )
    (net (code "139") (name "unconnected-(X2-Padc3)") (class "Default")
      (node (ref "X2") (pin "c3") (pinfunction "c3_c3") (pintype "power_in"))
    )
    (net (code "140") (name "unconnected-(X2-Padc4)") (class "Default")
      (node (ref "X2") (pin "c4") (pinfunction "c4_c4") (pintype "power_in"))
    )
  )
)
